# pcb_control_m128.net
KiCad netlist of a schematic drawn in EAGLE
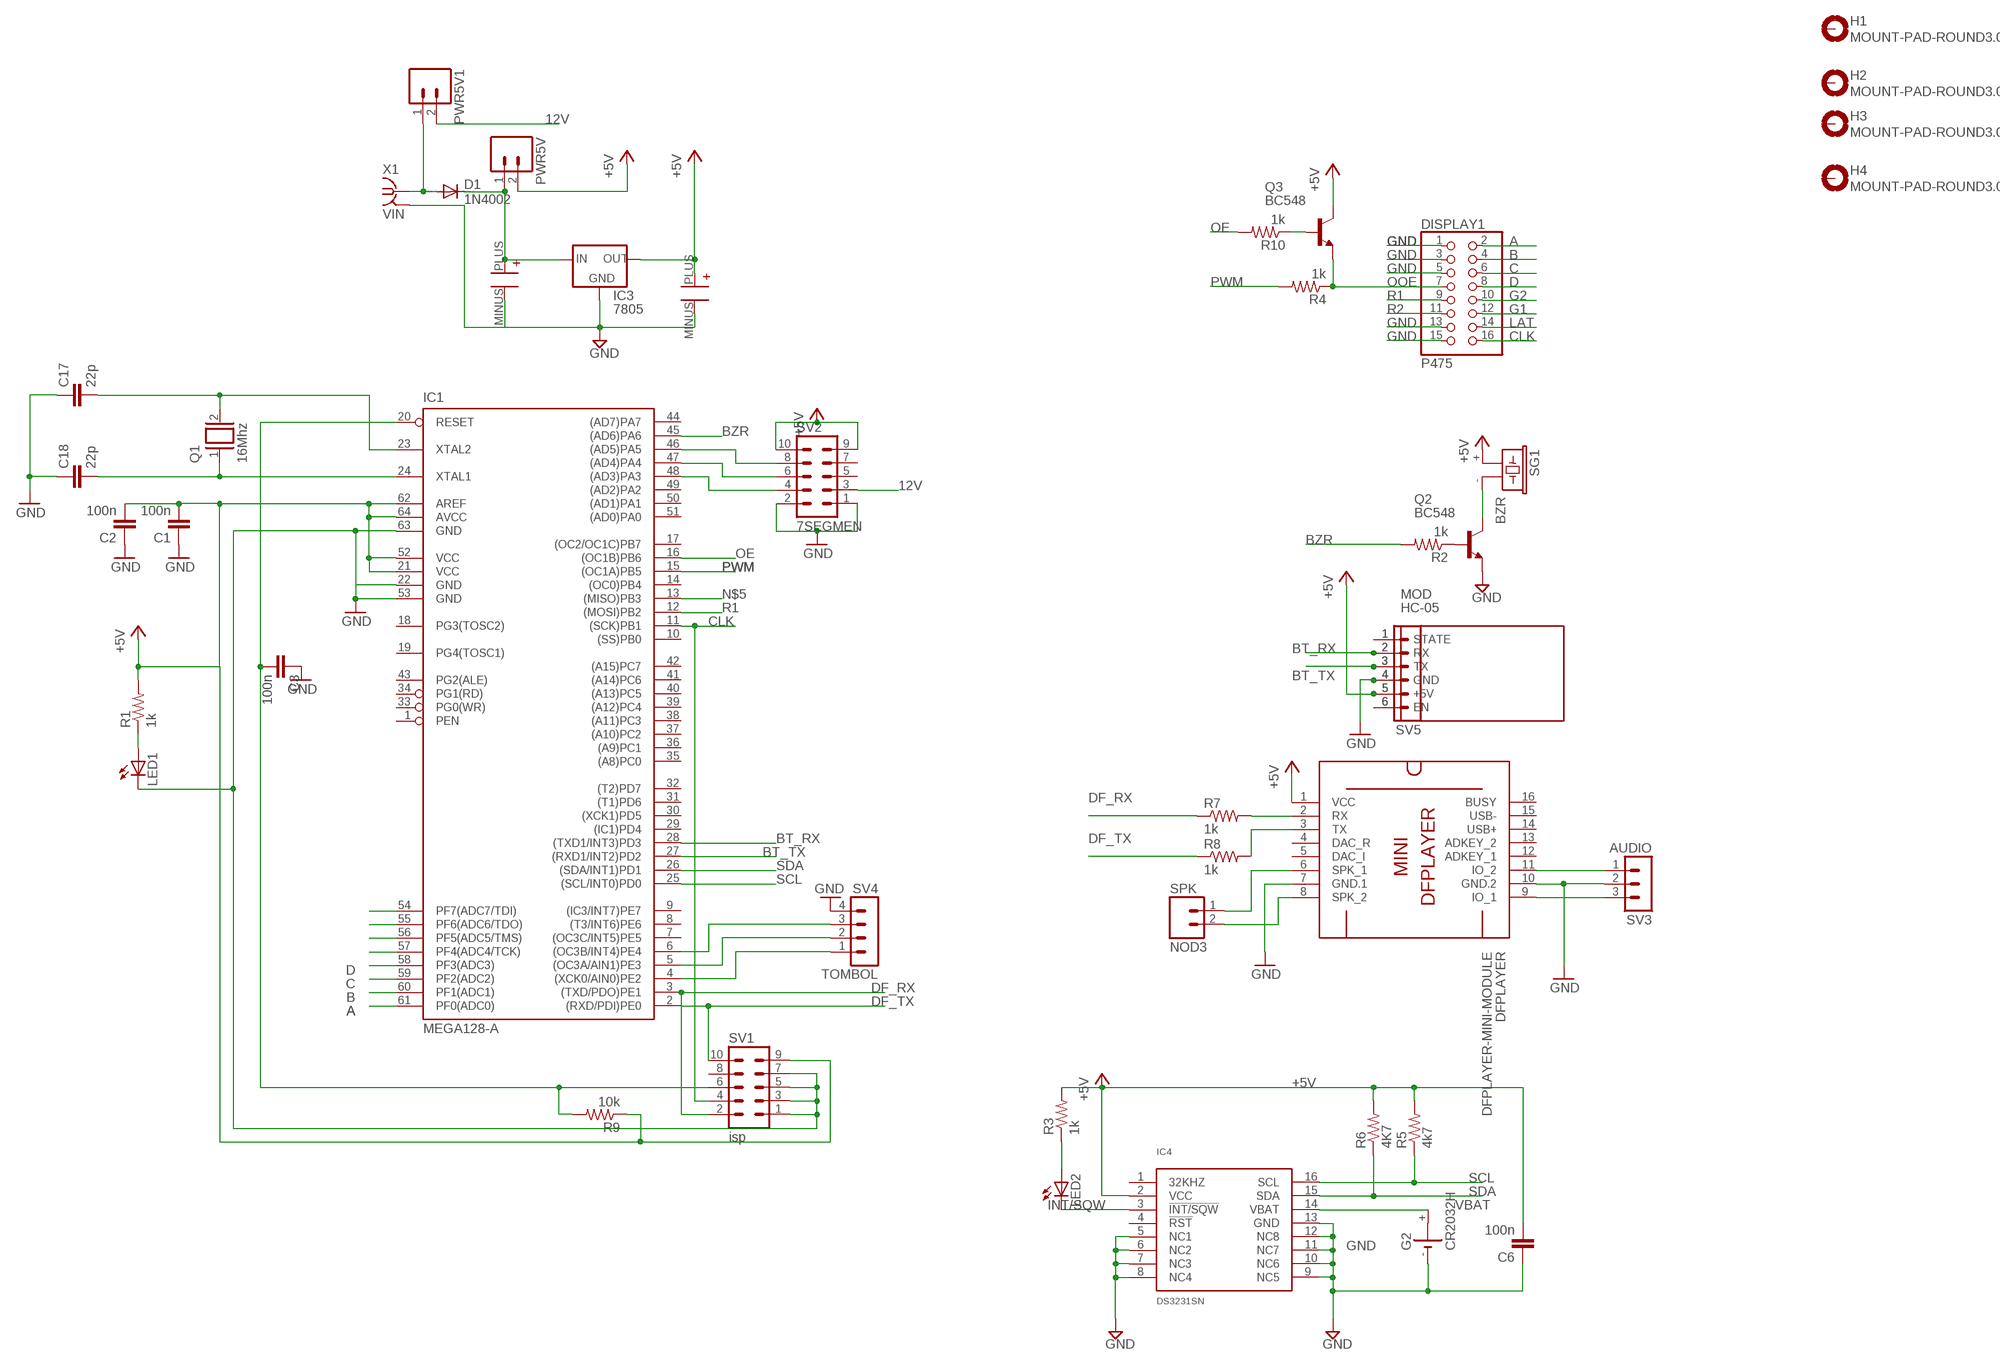
[diagram p0: schematic, sheet 1]

(export (version "E")
  (design (tool "Eeschema 10.0.6"))
  (components
    (comp (ref "C1")
      (value "100n")
      (footprint "eagle-import:C025-024X044")
      (libsource (lib "eagle-import") (part "C-EU025-024X044"))
    )
    (comp (ref "C2")
      (value "100n")
      (footprint "eagle-import:C025-024X044")
      (libsource (lib "eagle-import") (part "C-EU025-024X044"))
    )
    (comp (ref "C3")
      (value "100n")
      (footprint "eagle-import:C025-024X044")
      (libsource (lib "eagle-import") (part "C-EU025-024X044"))
    )
    (comp (ref "C6")
      (value "100n")
      (footprint "eagle-import:C025-024X044")
      (libsource (lib "eagle-import") (part "C-EU025-024X044"))
    )
    (comp (ref "C17")
      (value "22p")
      (footprint "eagle-import:C025-024X044")
      (libsource (lib "eagle-import") (part "C-EU025-024X044"))
    )
    (comp (ref "C18")
      (value "22p")
      (footprint "eagle-import:C025-024X044")
      (libsource (lib "eagle-import") (part "C-EU025-024X044"))
    )
    (comp (ref "C23")
      (value "470U")
      (footprint "eagle-import:EEU-FR1C471B")
      (libsource (lib "eagle-import") (part "EEU-FR1C471B"))
    )
    (comp (ref "C24")
      (value "1000U")
      (footprint "eagle-import:EEU-FR1C471B")
      (libsource (lib "eagle-import") (part "EEU-FR1C471B"))
    )
    (comp (ref "D1")
      (value "1N4002")
      (footprint "eagle-import:DO35-10")
      (libsource (lib "eagle-import") (part "1N4148DO35-10"))
    )
    (comp (ref "DFPLAYER")
      (value "DFPLAYER-MINI-MODULE")
      (footprint "eagle-import:DFPLAYER-MINI-MODULE")
      (libsource (lib "eagle-import") (part "DFPLAYER-MINI-MODULE"))
    )
    (comp (ref "DISPLAY1")
      (value "P475")
      (footprint "eagle-import:2X08")
      (libsource (lib "eagle-import") (part "PINHD-2X8"))
    )
    (comp (ref "G2")
      (value "CR2032H")
      (footprint "eagle-import:CR2032H")
      (libsource (lib "eagle-import") (part "CR2032H"))
    )
    (comp (ref "H1")
      (value "MOUNT-PAD-ROUND3.0")
      (footprint "eagle-import:3,0-PAD")
      (libsource (lib "eagle-import") (part "MOUNT-PAD-ROUND3.0"))
    )
    (comp (ref "H2")
      (value "MOUNT-PAD-ROUND3.0")
      (footprint "eagle-import:3,0-PAD")
      (libsource (lib "eagle-import") (part "MOUNT-PAD-ROUND3.0"))
    )
    (comp (ref "H3")
      (value "MOUNT-PAD-ROUND3.0")
      (footprint "eagle-import:3,0-PAD")
      (libsource (lib "eagle-import") (part "MOUNT-PAD-ROUND3.0"))
    )
    (comp (ref "H4")
      (value "MOUNT-PAD-ROUND3.0")
      (footprint "eagle-import:3,0-PAD")
      (libsource (lib "eagle-import") (part "MOUNT-PAD-ROUND3.0"))
    )
    (comp (ref "IC1")
      (value "MEGA128-A")
      (footprint "eagle-import:TQFP64")
      (fields (field (name "MPN") "ATMEGA128-16AU"))
      (libsource (lib "eagle-import") (part "MEGA128-A"))
    )
    (comp (ref "IC3")
      (value "7805")
      (footprint "eagle-import:78XXS")
      (libsource (lib "eagle-import") (part "78XXS"))
    )
    (comp (ref "IC4")
      (value "DS3231SN")
      (footprint "eagle-import:SO16W")
      (libsource (lib "eagle-import") (part "DS3231SN"))
    )
    (comp (ref "LED1")
      (value "LED3MM")
      (footprint "eagle-import:LED3MM")
      (libsource (lib "eagle-import") (part "LED3MM"))
    )
    (comp (ref "LED2")
      (value "LED3MM")
      (footprint "eagle-import:LED3MM")
      (libsource (lib "eagle-import") (part "LED3MM"))
    )
    (comp (ref "MOD")
      (value "HC-05")
      (footprint "eagle-import:WIRELESS-BLUETOOTH-HC-05")
      (libsource (lib "eagle-import") (part "WIRELESS-BLUETOOTH-HC-05"))
    )
    (comp (ref "NOD3")
      (value "SPK")
      (footprint "eagle-import:1X02")
      (libsource (lib "eagle-import") (part "M02PTH"))
    )
    (comp (ref "PWR5V")
      (value "M02PTH")
      (footprint "eagle-import:1X02")
      (libsource (lib "eagle-import") (part "M02PTH"))
    )
    (comp (ref "PWR5V1")
      (value "M02PTH")
      (footprint "eagle-import:1X02")
      (libsource (lib "eagle-import") (part "M02PTH"))
    )
    (comp (ref "Q1")
      (value "16Mhz")
      (footprint "eagle-import:QS")
      (libsource (lib "eagle-import") (part "XTAL/S"))
    )
    (comp (ref "Q2")
      (value "BC548")
      (footprint "eagle-import:TO92-EBC")
      (libsource (lib "eagle-import") (part "BC548"))
    )
    (comp (ref "Q3")
      (value "BC548")
      (footprint "eagle-import:TO92-EBC")
      (libsource (lib "eagle-import") (part "BC548"))
    )
    (comp (ref "R1")
      (value "1k")
      (footprint "eagle-import:AXIAL-0.3")
      (libsource (lib "eagle-import") (part "RESISTORAXIAL-0.3"))
    )
    (comp (ref "R2")
      (value "1k")
      (footprint "eagle-import:AXIAL-0.3")
      (libsource (lib "eagle-import") (part "RESISTORAXIAL-0.3"))
    )
    (comp (ref "R3")
      (value "1k")
      (footprint "eagle-import:AXIAL-0.3")
      (libsource (lib "eagle-import") (part "RESISTORAXIAL-0.3"))
    )
    (comp (ref "R4")
      (value "1k")
      (footprint "eagle-import:AXIAL-0.3")
      (libsource (lib "eagle-import") (part "RESISTORAXIAL-0.3"))
    )
    (comp (ref "R5")
      (value "4k7")
      (footprint "eagle-import:AXIAL-0.3")
      (libsource (lib "eagle-import") (part "RESISTORAXIAL-0.3"))
    )
    (comp (ref "R6")
      (value "4K7")
      (footprint "eagle-import:AXIAL-0.3")
      (libsource (lib "eagle-import") (part "RESISTORAXIAL-0.3"))
    )
    (comp (ref "R7")
      (value "1k")
      (footprint "eagle-import:AXIAL-0.3")
      (libsource (lib "eagle-import") (part "RESISTORAXIAL-0.3"))
    )
    (comp (ref "R8")
      (value "1k")
      (footprint "eagle-import:AXIAL-0.3")
      (libsource (lib "eagle-import") (part "RESISTORAXIAL-0.3"))
    )
    (comp (ref "R9")
      (value "10k")
      (footprint "eagle-import:AXIAL-0.3")
      (libsource (lib "eagle-import") (part "RESISTORAXIAL-0.3"))
    )
    (comp (ref "R10")
      (value "1k")
      (footprint "eagle-import:AXIAL-0.3")
      (libsource (lib "eagle-import") (part "RESISTORAXIAL-0.3"))
    )
    (comp (ref "SG1")
      (value "BZR")
      (footprint "eagle-import:F_CM12P")
      (libsource (lib "eagle-import") (part "F/CM12P"))
    )
    (comp (ref "SV1")
      (value "isp")
      (footprint "eagle-import:MA05-2")
      (libsource (lib "eagle-import") (part "MA05-2"))
    )
    (comp (ref "SV2")
      (value "7SEGMEN")
      (footprint "eagle-import:MA05-2")
      (libsource (lib "eagle-import") (part "MA05-2"))
    )
    (comp (ref "SV3")
      (value "AUDIO")
      (footprint "eagle-import:MA03-1")
      (libsource (lib "eagle-import") (part "MA03-1"))
    )
    (comp (ref "SV4")
      (value "TOMBOL")
      (footprint "eagle-import:MA04-1")
      (libsource (lib "eagle-import") (part "MA04-1"))
    )
    (comp (ref "SV5")
      (value "MA06-1")
      (footprint "eagle-import:MA06-1")
      (libsource (lib "eagle-import") (part "MA06-1"))
    )
    (comp (ref "X1")
      (value "VIN")
      (footprint "eagle-import:J502-ND")
      (libsource (lib "eagle-import") (part "SMA-J502-ND"))
    )
  )
  (nets
    (net (code "1") (name "+5V") (class "Default")
      (node (ref "C1") (pin "2") (pinfunction "2_2") (pintype "passive"))
      (node (ref "C2") (pin "2") (pinfunction "2_2") (pintype "passive"))
      (node (ref "C23") (pin "PLUS") (pinfunction "PLUS_PLUS") (pintype "bidirectional"))
      (node (ref "C6") (pin "2") (pinfunction "2_2") (pintype "passive"))
      (node (ref "DFPLAYER") (pin "1") (pinfunction "VCC_1") (pintype "power_in"))
      (node (ref "IC1") (pin "21") (pinfunction "VCC_21") (pintype "power_in"))
      (node (ref "IC1") (pin "52") (pinfunction "VCC_52") (pintype "power_in"))
      (node (ref "IC1") (pin "62") (pinfunction "AREF_62") (pintype "passive"))
      (node (ref "IC1") (pin "64") (pinfunction "AVCC_64") (pintype "power_in"))
      (node (ref "IC3") (pin "OUT") (pinfunction "OUT_OUT") (pintype "passive"))
      (node (ref "IC4") (pin "2") (pinfunction "VCC_2") (pintype "bidirectional"))
      (node (ref "MOD") (pin "5") (pinfunction "+5V_5") (pintype "power_in"))
      (node (ref "PWR5V") (pin "2") (pinfunction "2_2") (pintype "passive"))
      (node (ref "Q3") (pin "C") (pinfunction "C_C") (pintype "passive"))
      (node (ref "R1") (pin "P$2") (pinfunction "2_P$2") (pintype "passive"))
      (node (ref "R3") (pin "P$2") (pinfunction "2_P$2") (pintype "passive"))
      (node (ref "R5") (pin "P$2") (pinfunction "2_P$2") (pintype "passive"))
      (node (ref "R6") (pin "P$2") (pinfunction "2_P$2") (pintype "passive"))
      (node (ref "R9") (pin "P$1") (pinfunction "1_P$1") (pintype "passive"))
      (node (ref "SG1") (pin "+") (pinfunction "1_+") (pintype "passive"))
      (node (ref "SV1") (pin "9") (pinfunction "9_9") (pintype "passive"))
      (node (ref "SV2") (pin "10") (pinfunction "10_10") (pintype "passive"))
      (node (ref "SV2") (pin "9") (pinfunction "9_9") (pintype "passive"))
      (node (ref "SV5") (pin "5") (pinfunction "5_5") (pintype "passive"))
    )
    (net (code "2") (name "/12V") (class "Default")
      (node (ref "PWR5V1") (pin "2") (pinfunction "2_2") (pintype "passive"))
      (node (ref "SV2") (pin "3") (pinfunction "3_3") (pintype "passive"))
    )
    (net (code "3") (name "/A") (class "Default")
      (node (ref "DISPLAY1") (pin "2") (pinfunction "2_2") (pintype "passive"))
      (node (ref "IC1") (pin "61") (pinfunction "PF0(ADC0)_61") (pintype "input"))
    )
    (net (code "4") (name "/B") (class "Default")
      (node (ref "DISPLAY1") (pin "4") (pinfunction "4_4") (pintype "passive"))
      (node (ref "IC1") (pin "60") (pinfunction "PF1(ADC1)_60") (pintype "input"))
    )
    (net (code "5") (name "/BT_RX") (class "Default")
      (node (ref "IC1") (pin "28") (pinfunction "(TXD1/INT3)PD3_28") (pintype "bidirectional"))
      (node (ref "MOD") (pin "2") (pinfunction "RX_2") (pintype "bidirectional"))
      (node (ref "SV5") (pin "2") (pinfunction "2_2") (pintype "passive"))
    )
    (net (code "6") (name "/BT_TX") (class "Default")
      (node (ref "IC1") (pin "27") (pinfunction "(RXD1/INT2)PD2_27") (pintype "bidirectional"))
      (node (ref "MOD") (pin "3") (pinfunction "TX_3") (pintype "bidirectional"))
      (node (ref "SV5") (pin "3") (pinfunction "3_3") (pintype "passive"))
    )
    (net (code "7") (name "/BZR") (class "Default")
      (node (ref "IC1") (pin "45") (pinfunction "(AD6)PA6_45") (pintype "bidirectional"))
      (node (ref "R2") (pin "P$2") (pinfunction "2_P$2") (pintype "passive"))
    )
    (net (code "8") (name "/C") (class "Default")
      (node (ref "DISPLAY1") (pin "6") (pinfunction "6_6") (pintype "passive"))
      (node (ref "IC1") (pin "59") (pinfunction "PF2(ADC2)_59") (pintype "input"))
    )
    (net (code "9") (name "/CLK") (class "Default")
      (node (ref "DISPLAY1") (pin "16") (pinfunction "16_16") (pintype "passive"))
      (node (ref "IC1") (pin "11") (pinfunction "(SCK)PB1_11") (pintype "bidirectional"))
      (node (ref "SV1") (pin "4") (pinfunction "4_4") (pintype "passive"))
    )
    (net (code "10") (name "/D") (class "Default")
      (node (ref "DISPLAY1") (pin "8") (pinfunction "8_8") (pintype "passive"))
      (node (ref "IC1") (pin "58") (pinfunction "PF3(ADC3)_58") (pintype "input"))
    )
    (net (code "11") (name "/DF_RX") (class "Default")
      (node (ref "IC1") (pin "3") (pinfunction "(TXD/PDO)PE1_3") (pintype "bidirectional"))
      (node (ref "R7") (pin "P$1") (pinfunction "1_P$1") (pintype "passive"))
      (node (ref "SV1") (pin "2") (pinfunction "2_2") (pintype "passive"))
    )
    (net (code "12") (name "/DF_TX") (class "Default")
      (node (ref "IC1") (pin "2") (pinfunction "(RXD/PDI)PE0_2") (pintype "bidirectional"))
      (node (ref "R8") (pin "P$1") (pinfunction "1_P$1") (pintype "passive"))
      (node (ref "SV1") (pin "10") (pinfunction "10_10") (pintype "passive"))
    )
    (net (code "13") (name "/G1") (class "Default")
      (node (ref "DISPLAY1") (pin "12") (pinfunction "12_12") (pintype "passive"))
    )
    (net (code "14") (name "/G2") (class "Default")
      (node (ref "DISPLAY1") (pin "10") (pinfunction "10_10") (pintype "passive"))
    )
    (net (code "15") (name "/INT{slash}SQW") (class "Default")
      (node (ref "IC4") (pin "3") (pinfunction "~{INT/SQW}_3") (pintype "bidirectional"))
      (node (ref "LED2") (pin "K") (pinfunction "C_K") (pintype "passive"))
    )
    (net (code "16") (name "/LAT") (class "Default")
      (node (ref "DISPLAY1") (pin "14") (pinfunction "14_14") (pintype "passive"))
      (node (ref "IC1") (pin "57") (pinfunction "PF4(ADC4/TCK)_57") (pintype "input"))
    )
    (net (code "17") (name "/N$5") (class "Default")
      (node (ref "IC1") (pin "13") (pinfunction "(MISO)PB3_13") (pintype "bidirectional"))
    )
    (net (code "18") (name "/OE") (class "Default")
      (node (ref "IC1") (pin "16") (pinfunction "(OC1B)PB6_16") (pintype "bidirectional"))
      (node (ref "R10") (pin "P$2") (pinfunction "2_P$2") (pintype "passive"))
    )
    (net (code "19") (name "/OOE") (class "Default")
      (node (ref "DISPLAY1") (pin "7") (pinfunction "7_7") (pintype "passive"))
      (node (ref "Q3") (pin "E") (pinfunction "E_E") (pintype "passive"))
      (node (ref "R4") (pin "P$1") (pinfunction "1_P$1") (pintype "passive"))
    )
    (net (code "20") (name "/PWM") (class "Default")
      (node (ref "IC1") (pin "15") (pinfunction "(OC1A)PB5_15") (pintype "bidirectional"))
      (node (ref "R4") (pin "P$2") (pinfunction "2_P$2") (pintype "passive"))
    )
    (net (code "21") (name "/R1") (class "Default")
      (node (ref "DISPLAY1") (pin "9") (pinfunction "9_9") (pintype "passive"))
      (node (ref "IC1") (pin "12") (pinfunction "(MOSI)PB2_12") (pintype "bidirectional"))
    )
    (net (code "22") (name "/R2") (class "Default")
      (node (ref "DISPLAY1") (pin "11") (pinfunction "11_11") (pintype "passive"))
    )
    (net (code "23") (name "/SCL") (class "Default")
      (node (ref "IC1") (pin "25") (pinfunction "(SCL/INT0)PD0_25") (pintype "bidirectional"))
      (node (ref "IC4") (pin "16") (pinfunction "SCL_16") (pintype "bidirectional"))
      (node (ref "R5") (pin "P$1") (pinfunction "1_P$1") (pintype "passive"))
    )
    (net (code "24") (name "/SDA") (class "Default")
      (node (ref "IC1") (pin "26") (pinfunction "(SDA/INT1)PD1_26") (pintype "bidirectional"))
      (node (ref "IC4") (pin "15") (pinfunction "SDA_15") (pintype "bidirectional"))
      (node (ref "R6") (pin "P$1") (pinfunction "1_P$1") (pintype "passive"))
    )
    (net (code "25") (name "/VBAT") (class "Default")
      (node (ref "G2") (pin "+") (pinfunction "+_+") (pintype "passive"))
      (node (ref "IC4") (pin "14") (pinfunction "VBAT_14") (pintype "bidirectional"))
    )
    (net (code "26") (name "GND") (class "Default")
      (node (ref "C1") (pin "1") (pinfunction "1_1") (pintype "passive"))
      (node (ref "C17") (pin "1") (pinfunction "1_1") (pintype "passive"))
      (node (ref "C18") (pin "1") (pinfunction "1_1") (pintype "passive"))
      (node (ref "C2") (pin "1") (pinfunction "1_1") (pintype "passive"))
      (node (ref "C23") (pin "MINUS") (pinfunction "MINUS_MINUS") (pintype "bidirectional"))
      (node (ref "C24") (pin "MINUS") (pinfunction "MINUS_MINUS") (pintype "bidirectional"))
      (node (ref "C3") (pin "1") (pinfunction "1_1") (pintype "passive"))
      (node (ref "C6") (pin "1") (pinfunction "1_1") (pintype "passive"))
      (node (ref "DFPLAYER") (pin "10") (pinfunction "GND.2_10") (pintype "power_in"))
      (node (ref "DFPLAYER") (pin "7") (pinfunction "GND.1_7") (pintype "power_in"))
      (node (ref "DISPLAY1") (pin "1") (pinfunction "1_1") (pintype "passive"))
      (node (ref "DISPLAY1") (pin "13") (pinfunction "13_13") (pintype "passive"))
      (node (ref "DISPLAY1") (pin "15") (pinfunction "15_15") (pintype "passive"))
      (node (ref "DISPLAY1") (pin "3") (pinfunction "3_3") (pintype "passive"))
      (node (ref "DISPLAY1") (pin "5") (pinfunction "5_5") (pintype "passive"))
      (node (ref "G2") (pin "-") (pinfunction "-_-") (pintype "passive"))
      (node (ref "IC1") (pin "22") (pinfunction "GND_22") (pintype "power_in"))
      (node (ref "IC1") (pin "53") (pinfunction "GND_53") (pintype "power_in"))
      (node (ref "IC1") (pin "63") (pinfunction "GND_63") (pintype "power_in"))
      (node (ref "IC3") (pin "GND") (pinfunction "GND_GND") (pintype "input"))
      (node (ref "IC4") (pin "10") (pinfunction "NC6_10") (pintype "bidirectional"))
      (node (ref "IC4") (pin "11") (pinfunction "NC7_11") (pintype "bidirectional"))
      (node (ref "IC4") (pin "12") (pinfunction "NC8_12") (pintype "bidirectional"))
      (node (ref "IC4") (pin "13") (pinfunction "GND_13") (pintype "bidirectional"))
      (node (ref "IC4") (pin "5") (pinfunction "NC1_5") (pintype "bidirectional"))
      (node (ref "IC4") (pin "6") (pinfunction "NC2_6") (pintype "bidirectional"))
      (node (ref "IC4") (pin "7") (pinfunction "NC3_7") (pintype "bidirectional"))
      (node (ref "IC4") (pin "8") (pinfunction "NC4_8") (pintype "bidirectional"))
      (node (ref "IC4") (pin "9") (pinfunction "NC5_9") (pintype "bidirectional"))
      (node (ref "LED1") (pin "K") (pinfunction "C_K") (pintype "passive"))
      (node (ref "MOD") (pin "4") (pinfunction "GND_4") (pintype "power_in"))
      (node (ref "Q2") (pin "E") (pinfunction "E_E") (pintype "passive"))
      (node (ref "SV1") (pin "1") (pinfunction "1_1") (pintype "passive"))
      (node (ref "SV1") (pin "3") (pinfunction "3_3") (pintype "passive"))
      (node (ref "SV1") (pin "5") (pinfunction "5_5") (pintype "passive"))
      (node (ref "SV1") (pin "7") (pinfunction "7_7") (pintype "passive"))
      (node (ref "SV2") (pin "1") (pinfunction "1_1") (pintype "passive"))
      (node (ref "SV2") (pin "2") (pinfunction "2_2") (pintype "passive"))
      (node (ref "SV3") (pin "2") (pinfunction "2_2") (pintype "passive"))
      (node (ref "SV4") (pin "4") (pinfunction "4_4") (pintype "passive"))
      (node (ref "SV5") (pin "4") (pinfunction "4_4") (pintype "passive"))
      (node (ref "X1") (pin "2") (pinfunction "2_2") (pintype "passive"))
      (node (ref "X1") (pin "5") (pinfunction "2_5") (pintype "passive"))
    )
    (net (code "27") (name "Net-(C24-PadPLUS)") (class "Default")
      (node (ref "C24") (pin "PLUS") (pinfunction "PLUS_PLUS") (pintype "bidirectional"))
      (node (ref "D1") (pin "C") (pinfunction "C_C") (pintype "passive"))
      (node (ref "IC3") (pin "IN") (pinfunction "IN_IN") (pintype "input"))
      (node (ref "PWR5V") (pin "1") (pinfunction "1_1") (pintype "passive"))
    )
    (net (code "28") (name "Net-(D1-PadA)") (class "Default")
      (node (ref "D1") (pin "A") (pinfunction "A_A") (pintype "passive"))
      (node (ref "PWR5V1") (pin "1") (pinfunction "1_1") (pintype "passive"))
      (node (ref "X1") (pin "3") (pinfunction "1_3") (pintype "passive"))
      (node (ref "X1") (pin "4") (pinfunction "1_4") (pintype "passive"))
    )
    (net (code "29") (name "Net-(DFPLAYER-IO_1)") (class "Default")
      (node (ref "DFPLAYER") (pin "9") (pinfunction "IO_1_9") (pintype "bidirectional"))
      (node (ref "SV3") (pin "3") (pinfunction "3_3") (pintype "passive"))
    )
    (net (code "30") (name "Net-(DFPLAYER-IO_2)") (class "Default")
      (node (ref "DFPLAYER") (pin "11") (pinfunction "IO_2_11") (pintype "bidirectional"))
      (node (ref "SV3") (pin "1") (pinfunction "1_1") (pintype "passive"))
    )
    (net (code "31") (name "Net-(DFPLAYER-RX)") (class "Default")
      (node (ref "DFPLAYER") (pin "2") (pinfunction "RX_2") (pintype "bidirectional"))
      (node (ref "R7") (pin "P$2") (pinfunction "2_P$2") (pintype "passive"))
    )
    (net (code "32") (name "Net-(DFPLAYER-SPK_1)") (class "Default")
      (node (ref "DFPLAYER") (pin "6") (pinfunction "SPK_1_6") (pintype "bidirectional"))
      (node (ref "NOD3") (pin "1") (pinfunction "1_1") (pintype "passive"))
    )
    (net (code "33") (name "Net-(DFPLAYER-SPK_2)") (class "Default")
      (node (ref "DFPLAYER") (pin "8") (pinfunction "SPK_2_8") (pintype "bidirectional"))
      (node (ref "NOD3") (pin "2") (pinfunction "2_2") (pintype "passive"))
    )
    (net (code "34") (name "Net-(DFPLAYER-TX)") (class "Default")
      (node (ref "DFPLAYER") (pin "3") (pinfunction "TX_3") (pintype "bidirectional"))
      (node (ref "R8") (pin "P$2") (pinfunction "2_P$2") (pintype "passive"))
    )
    (net (code "35") (name "Net-(IC1-(AD3)PA3)") (class "Default")
      (node (ref "IC1") (pin "48") (pinfunction "(AD3)PA3_48") (pintype "bidirectional"))
      (node (ref "SV2") (pin "4") (pinfunction "4_4") (pintype "passive"))
    )
    (net (code "36") (name "Net-(IC1-(AD4)PA4)") (class "Default")
      (node (ref "IC1") (pin "47") (pinfunction "(AD4)PA4_47") (pintype "bidirectional"))
      (node (ref "SV2") (pin "6") (pinfunction "6_6") (pintype "passive"))
    )
    (net (code "37") (name "Net-(IC1-(AD5)PA5)") (class "Default")
      (node (ref "IC1") (pin "46") (pinfunction "(AD5)PA5_46") (pintype "bidirectional"))
      (node (ref "SV2") (pin "8") (pinfunction "8_8") (pintype "passive"))
    )
    (net (code "38") (name "Net-(IC1-(OC3A{slash}AIN1)PE3)") (class "Default")
      (node (ref "IC1") (pin "5") (pinfunction "(OC3A/AIN1)PE3_5") (pintype "bidirectional"))
      (node (ref "SV4") (pin "2") (pinfunction "2_2") (pintype "passive"))
    )
    (net (code "39") (name "Net-(IC1-(OC3B{slash}INT4)PE4)") (class "Default")
      (node (ref "IC1") (pin "6") (pinfunction "(OC3B/INT4)PE4_6") (pintype "bidirectional"))
      (node (ref "SV4") (pin "3") (pinfunction "3_3") (pintype "passive"))
    )
    (net (code "40") (name "Net-(IC1-(XCK0{slash}AIN0)PE2)") (class "Default")
      (node (ref "IC1") (pin "4") (pinfunction "(XCK0/AIN0)PE2_4") (pintype "bidirectional"))
      (node (ref "SV4") (pin "1") (pinfunction "1_1") (pintype "passive"))
    )
    (net (code "41") (name "Net-(IC1-RESET)") (class "Default")
      (node (ref "C3") (pin "2") (pinfunction "2_2") (pintype "passive"))
      (node (ref "IC1") (pin "20") (pinfunction "RESET_20") (pintype "input"))
      (node (ref "R9") (pin "P$2") (pinfunction "2_P$2") (pintype "passive"))
      (node (ref "SV1") (pin "6") (pinfunction "6_6") (pintype "passive"))
    )
    (net (code "42") (name "Net-(IC1-XTAL1)") (class "Default")
      (node (ref "C18") (pin "2") (pinfunction "2_2") (pintype "passive"))
      (node (ref "IC1") (pin "24") (pinfunction "XTAL1_24") (pintype "bidirectional"))
      (node (ref "Q1") (pin "1") (pinfunction "1_1") (pintype "passive"))
    )
    (net (code "43") (name "Net-(IC1-XTAL2)") (class "Default")
      (node (ref "C17") (pin "2") (pinfunction "2_2") (pintype "passive"))
      (node (ref "IC1") (pin "23") (pinfunction "XTAL2_23") (pintype "bidirectional"))
      (node (ref "Q1") (pin "2") (pinfunction "2_2") (pintype "passive"))
    )
    (net (code "44") (name "Net-(MOD-EN)") (class "Default")
      (node (ref "MOD") (pin "6") (pinfunction "EN_6") (pintype "bidirectional"))
      (node (ref "SV5") (pin "6") (pinfunction "6_6") (pintype "passive"))
    )
    (net (code "45") (name "Net-(MOD-STATE)") (class "Default")
      (node (ref "MOD") (pin "1") (pinfunction "STATE_1") (pintype "bidirectional"))
      (node (ref "SV5") (pin "1") (pinfunction "1_1") (pintype "passive"))
    )
    (net (code "46") (name "Net-(R1-1)") (class "Default")
      (node (ref "LED1") (pin "A") (pinfunction "A_A") (pintype "passive"))
      (node (ref "R1") (pin "P$1") (pinfunction "1_P$1") (pintype "passive"))
    )
    (net (code "47") (name "Net-(R2-1)") (class "Default")
      (node (ref "Q2") (pin "B") (pinfunction "B_B") (pintype "passive"))
      (node (ref "R2") (pin "P$1") (pinfunction "1_P$1") (pintype "passive"))
    )
    (net (code "48") (name "Net-(R3-1)") (class "Default")
      (node (ref "LED2") (pin "A") (pinfunction "A_A") (pintype "passive"))
      (node (ref "R3") (pin "P$1") (pinfunction "1_P$1") (pintype "passive"))
    )
    (net (code "49") (name "Net-(R10-1)") (class "Default")
      (node (ref "Q3") (pin "B") (pinfunction "B_B") (pintype "passive"))
      (node (ref "R10") (pin "P$1") (pinfunction "1_P$1") (pintype "passive"))
    )
    (net (code "50") (name "Net-(SG1-2)") (class "Default")
      (node (ref "Q2") (pin "C") (pinfunction "C_C") (pintype "passive"))
      (node (ref "SG1") (pin "-") (pinfunction "2_-") (pintype "passive"))
    )
    (net (code "51") (name "unconnected-(DFPLAYER-ADKEY_1-Pad12)") (class "Default")
      (node (ref "DFPLAYER") (pin "12") (pinfunction "ADKEY_1_12") (pintype "bidirectional"))
    )
    (net (code "52") (name "unconnected-(DFPLAYER-ADKEY_2-Pad13)") (class "Default")
      (node (ref "DFPLAYER") (pin "13") (pinfunction "ADKEY_2_13") (pintype "bidirectional"))
    )
    (net (code "53") (name "unconnected-(DFPLAYER-BUSY-Pad16)") (class "Default")
      (node (ref "DFPLAYER") (pin "16") (pinfunction "BUSY_16") (pintype "bidirectional"))
    )
    (net (code "54") (name "unconnected-(DFPLAYER-DAC_I-Pad5)") (class "Default")
      (node (ref "DFPLAYER") (pin "5") (pinfunction "DAC_I_5") (pintype "bidirectional"))
    )
    (net (code "55") (name "unconnected-(DFPLAYER-DAC_R-Pad4)") (class "Default")
      (node (ref "DFPLAYER") (pin "4") (pinfunction "DAC_R_4") (pintype "bidirectional"))
    )
    (net (code "56") (name "unconnected-(DFPLAYER-USB+-Pad14)") (class "Default")
      (node (ref "DFPLAYER") (pin "14") (pinfunction "USB+_14") (pintype "bidirectional"))
    )
    (net (code "57") (name "unconnected-(DFPLAYER-USB--Pad15)") (class "Default")
      (node (ref "DFPLAYER") (pin "15") (pinfunction "USB-_15") (pintype "bidirectional"))
    )
    (net (code "58") (name "unconnected-(H1-MOUNT-PadB3,0)") (class "Default")
      (node (ref "H1") (pin "B3,0") (pinfunction "MOUNT_B3,0") (pintype "passive"))
    )
    (net (code "59") (name "unconnected-(H2-MOUNT-PadB3,0)") (class "Default")
      (node (ref "H2") (pin "B3,0") (pinfunction "MOUNT_B3,0") (pintype "passive"))
    )
    (net (code "60") (name "unconnected-(H3-MOUNT-PadB3,0)") (class "Default")
      (node (ref "H3") (pin "B3,0") (pinfunction "MOUNT_B3,0") (pintype "passive"))
    )
    (net (code "61") (name "unconnected-(H4-MOUNT-PadB3,0)") (class "Default")
      (node (ref "H4") (pin "B3,0") (pinfunction "MOUNT_B3,0") (pintype "passive"))
    )
    (net (code "62") (name "unconnected-(IC1-(A8)PC0-Pad35)") (class "Default")
      (node (ref "IC1") (pin "35") (pinfunction "(A8)PC0_35") (pintype "output"))
    )
    (net (code "63") (name "unconnected-(IC1-(A9)PC1-Pad36)") (class "Default")
      (node (ref "IC1") (pin "36") (pinfunction "(A9)PC1_36") (pintype "output"))
    )
    (net (code "64") (name "unconnected-(IC1-(A10)PC2-Pad37)") (class "Default")
      (node (ref "IC1") (pin "37") (pinfunction "(A10)PC2_37") (pintype "output"))
    )
    (net (code "65") (name "unconnected-(IC1-(A11)PC3-Pad38)") (class "Default")
      (node (ref "IC1") (pin "38") (pinfunction "(A11)PC3_38") (pintype "output"))
    )
    (net (code "66") (name "unconnected-(IC1-(A12)PC4-Pad39)") (class "Default")
      (node (ref "IC1") (pin "39") (pinfunction "(A12)PC4_39") (pintype "output"))
    )
    (net (code "67") (name "unconnected-(IC1-(A13)PC5-Pad40)") (class "Default")
      (node (ref "IC1") (pin "40") (pinfunction "(A13)PC5_40") (pintype "output"))
    )
    (net (code "68") (name "unconnected-(IC1-(A14)PC6-Pad41)") (class "Default")
      (node (ref "IC1") (pin "41") (pinfunction "(A14)PC6_41") (pintype "output"))
    )
    (net (code "69") (name "unconnected-(IC1-(A15)PC7-Pad42)") (class "Default")
      (node (ref "IC1") (pin "42") (pinfunction "(A15)PC7_42") (pintype "output"))
    )
    (net (code "70") (name "unconnected-(IC1-(AD0)PA0-Pad51)") (class "Default")
      (node (ref "IC1") (pin "51") (pinfunction "(AD0)PA0_51") (pintype "bidirectional"))
    )
    (net (code "71") (name "unconnected-(IC1-(AD1)PA1-Pad50)") (class "Default")
      (node (ref "IC1") (pin "50") (pinfunction "(AD1)PA1_50") (pintype "bidirectional"))
    )
    (net (code "72") (name "unconnected-(IC1-(AD2)PA2-Pad49)") (class "Default")
      (node (ref "IC1") (pin "49") (pinfunction "(AD2)PA2_49") (pintype "bidirectional"))
    )
    (net (code "73") (name "unconnected-(IC1-(AD7)PA7-Pad44)") (class "Default")
      (node (ref "IC1") (pin "44") (pinfunction "(AD7)PA7_44") (pintype "bidirectional"))
    )
    (net (code "74") (name "unconnected-(IC1-(IC1)PD4-Pad29)") (class "Default")
      (node (ref "IC1") (pin "29") (pinfunction "(IC1)PD4_29") (pintype "bidirectional"))
    )
    (net (code "75") (name "unconnected-(IC1-(IC3{slash}INT7)PE7-Pad9)") (class "Default")
      (node (ref "IC1") (pin "9") (pinfunction "(IC3/INT7)PE7_9") (pintype "bidirectional"))
    )
    (net (code "76") (name "unconnected-(IC1-(OC0)PB4-Pad14)") (class "Default")
      (node (ref "IC1") (pin "14") (pinfunction "(OC0)PB4_14") (pintype "bidirectional"))
    )
    (net (code "77") (name "unconnected-(IC1-(OC2{slash}OC1C)PB7-Pad17)") (class "Default")
      (node (ref "IC1") (pin "17") (pinfunction "(OC2/OC1C)PB7_17") (pintype "bidirectional"))
    )
    (net (code "78") (name "unconnected-(IC1-(OC3C{slash}INT5)PE5-Pad7)") (class "Default")
      (node (ref "IC1") (pin "7") (pinfunction "(OC3C/INT5)PE5_7") (pintype "bidirectional"))
    )
    (net (code "79") (name "unconnected-(IC1-(SS)PB0-Pad10)") (class "Default")
      (node (ref "IC1") (pin "10") (pinfunction "(SS)PB0_10") (pintype "bidirectional"))
    )
    (net (code "80") (name "unconnected-(IC1-(T1)PD6-Pad31)") (class "Default")
      (node (ref "IC1") (pin "31") (pinfunction "(T1)PD6_31") (pintype "bidirectional"))
    )
    (net (code "81") (name "unconnected-(IC1-(T2)PD7-Pad32)") (class "Default")
      (node (ref "IC1") (pin "32") (pinfunction "(T2)PD7_32") (pintype "bidirectional"))
    )
    (net (code "82") (name "unconnected-(IC1-(T3{slash}INT6)PE6-Pad8)") (class "Default")
      (node (ref "IC1") (pin "8") (pinfunction "(T3/INT6)PE6_8") (pintype "bidirectional"))
    )
    (net (code "83") (name "unconnected-(IC1-(XCK1)PD5-Pad30)") (class "Default")
      (node (ref "IC1") (pin "30") (pinfunction "(XCK1)PD5_30") (pintype "bidirectional"))
    )
    (net (code "84") (name "unconnected-(IC1-PEN-Pad1)") (class "Default")
      (node (ref "IC1") (pin "1") (pinfunction "PEN_1") (pintype "input"))
    )
    (net (code "85") (name "unconnected-(IC1-PF5(ADC5{slash}TMS)-Pad56)") (class "Default")
      (node (ref "IC1") (pin "56") (pinfunction "PF5(ADC5/TMS)_56") (pintype "input"))
    )
    (net (code "86") (name "unconnected-(IC1-PF6(ADC6{slash}TDO)-Pad55)") (class "Default")
      (node (ref "IC1") (pin "55") (pinfunction "PF6(ADC6/TDO)_55") (pintype "input"))
    )
    (net (code "87") (name "unconnected-(IC1-PF7(ADC7{slash}TDI)-Pad54)") (class "Default")
      (node (ref "IC1") (pin "54") (pinfunction "PF7(ADC7/TDI)_54") (pintype "input"))
    )
    (net (code "88") (name "unconnected-(IC1-PG0(WR)-Pad33)") (class "Default")
      (node (ref "IC1") (pin "33") (pinfunction "PG0(WR)_33") (pintype "bidirectional"))
    )
    (net (code "89") (name "unconnected-(IC1-PG1(RD)-Pad34)") (class "Default")
      (node (ref "IC1") (pin "34") (pinfunction "PG1(RD)_34") (pintype "bidirectional"))
    )
    (net (code "90") (name "unconnected-(IC1-PG2(ALE)-Pad43)") (class "Default")
      (node (ref "IC1") (pin "43") (pinfunction "PG2(ALE)_43") (pintype "bidirectional"))
    )
    (net (code "91") (name "unconnected-(IC1-PG3(TOSC2)-Pad18)") (class "Default")
      (node (ref "IC1") (pin "18") (pinfunction "PG3(TOSC2)_18") (pintype "bidirectional"))
    )
    (net (code "92") (name "unconnected-(IC1-PG4(TOSC1)-Pad19)") (class "Default")
      (node (ref "IC1") (pin "19") (pinfunction "PG4(TOSC1)_19") (pintype "bidirectional"))
    )
    (net (code "93") (name "unconnected-(IC4-32KHZ-Pad1)") (class "Default")
      (node (ref "IC4") (pin "1") (pinfunction "32KHZ_1") (pintype "bidirectional"))
    )
    (net (code "94") (name "unconnected-(IC4-~{RST}-Pad4)") (class "Default")
      (node (ref "IC4") (pin "4") (pinfunction "~{RST}_4") (pintype "bidirectional"))
    )
    (net (code "95") (name "unconnected-(SV1-Pad8)") (class "Default")
      (node (ref "SV1") (pin "8") (pinfunction "8_8") (pintype "passive"))
    )
    (net (code "96") (name "unconnected-(SV2-Pad5)") (class "Default")
      (node (ref "SV2") (pin "5") (pinfunction "5_5") (pintype "passive"))
    )
    (net (code "97") (name "unconnected-(SV2-Pad7)") (class "Default")
      (node (ref "SV2") (pin "7") (pinfunction "7_7") (pintype "passive"))
    )
  )
)
